# Circuit_Complet_Carrer.net
KiCad netlist of a schematic drawn in Altium Designer
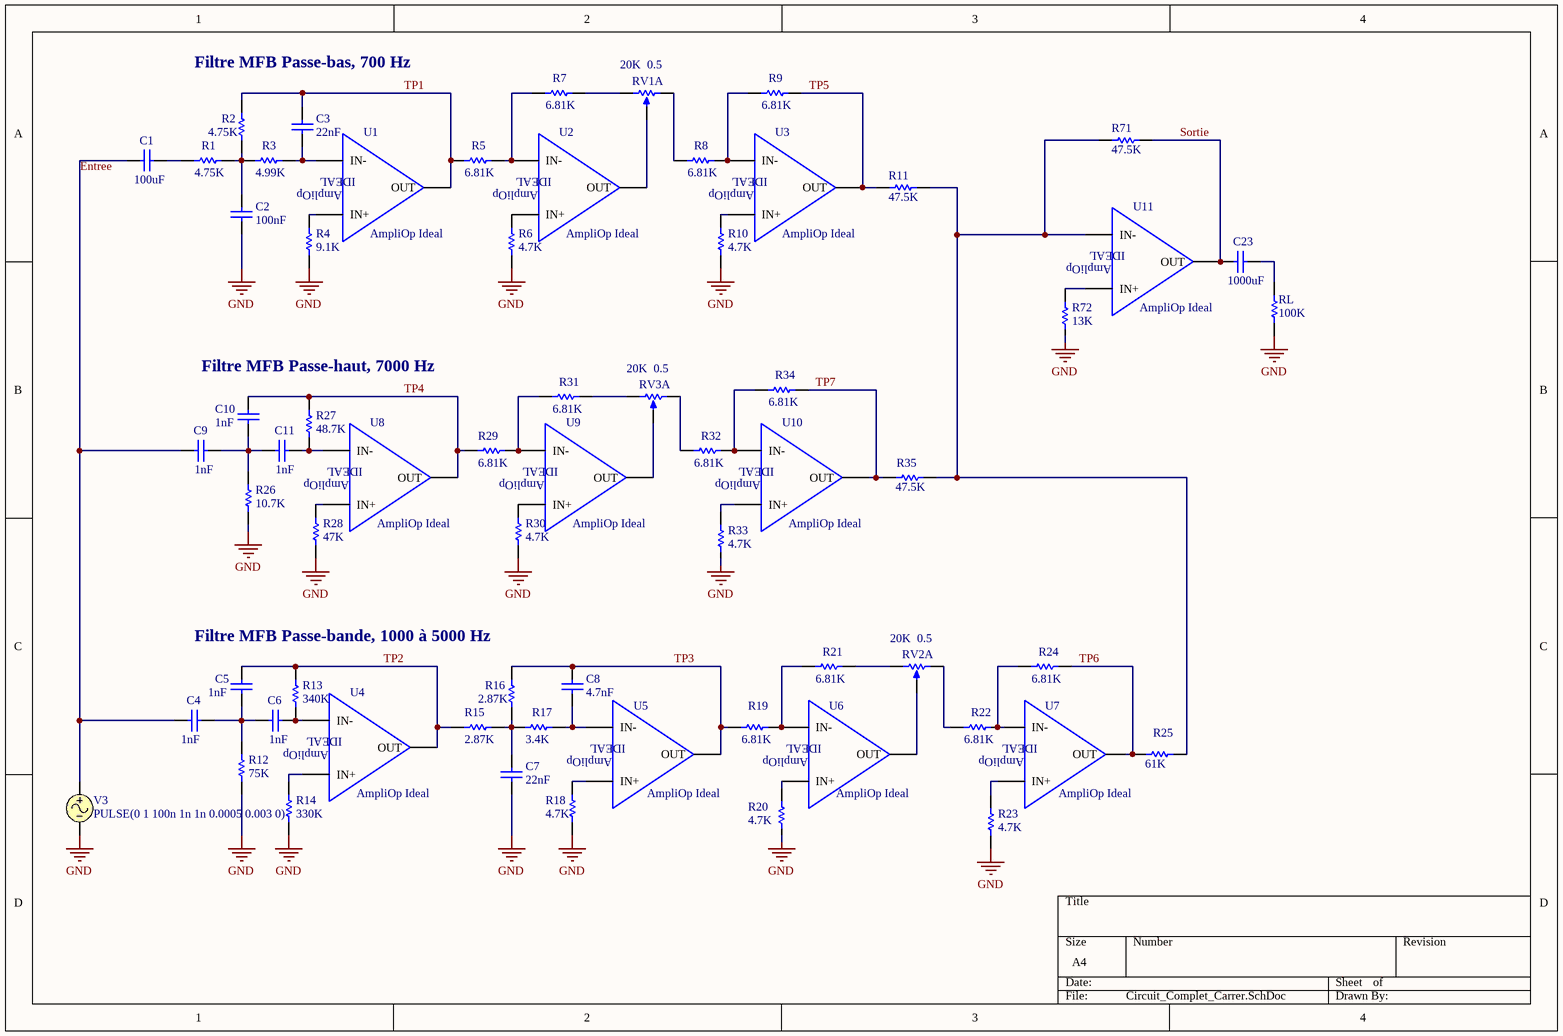
[diagram p0: Circuit_Complet_Carrer.SchDoc]

(export (version "E")
  (design (tool "Eeschema 10.0.6"))
  (components
    (comp (ref "C1")
      (value "100uF")
      (footprint "RAD-0.3")
      (description "Capacitor")
      (fields (field (name "Comment") "Cap") (field (name "PUBLISHER") "Altium Limited"))
      (libsource (lib "Miscellaneous Devices") (part "Cap"))
    )
    (comp (ref "C2")
      (value "100nF")
      (footprint "RAD-0.3")
      (description "Capacitor")
      (fields (field (name "Comment") "Cap") (field (name "PUBLISHER") "Altium Limited"))
      (libsource (lib "Miscellaneous Devices") (part "Cap"))
    )
    (comp (ref "C3")
      (value "22nF")
      (footprint "RAD-0.3")
      (description "Capacitor")
      (fields (field (name "Comment") "Cap") (field (name "PUBLISHER") "Altium Limited"))
      (libsource (lib "Miscellaneous Devices") (part "Cap"))
    )
    (comp (ref "C4")
      (value "1nF")
      (footprint "RAD-0.3")
      (description "Capacitor")
      (fields (field (name "Comment") "Cap") (field (name "PUBLISHER") "Altium Limited"))
      (libsource (lib "Miscellaneous Devices") (part "Cap"))
    )
    (comp (ref "C5")
      (value "1nF")
      (footprint "RAD-0.3")
      (description "Capacitor")
      (fields (field (name "Comment") "Cap") (field (name "PUBLISHER") "Altium Limited"))
      (libsource (lib "Miscellaneous Devices") (part "Cap"))
    )
    (comp (ref "C6")
      (value "1nF")
      (footprint "RAD-0.3")
      (description "Capacitor")
      (fields (field (name "Comment") "Cap") (field (name "PUBLISHER") "Altium Limited"))
      (libsource (lib "Miscellaneous Devices") (part "Cap"))
    )
    (comp (ref "C7")
      (value "22nF")
      (footprint "RAD-0.3")
      (description "Capacitor")
      (fields (field (name "Comment") "Cap") (field (name "PUBLISHER") "Altium Limited"))
      (libsource (lib "Miscellaneous Devices") (part "Cap"))
    )
    (comp (ref "C8")
      (value "4.7nF")
      (footprint "RAD-0.3")
      (description "Capacitor")
      (fields (field (name "Comment") "Cap") (field (name "PUBLISHER") "Altium Limited"))
      (libsource (lib "Miscellaneous Devices") (part "Cap"))
    )
    (comp (ref "C9")
      (value "1nF")
      (footprint "RAD-0.3")
      (description "Capacitor")
      (fields (field (name "Comment") "Cap") (field (name "PUBLISHER") "Altium Limited"))
      (libsource (lib "Miscellaneous Devices") (part "Cap"))
    )
    (comp (ref "C10")
      (value "1nF")
      (footprint "RAD-0.3")
      (description "Capacitor")
      (fields (field (name "Comment") "Cap") (field (name "PUBLISHER") "Altium Limited"))
      (libsource (lib "Miscellaneous Devices") (part "Cap"))
    )
    (comp (ref "C11")
      (value "1nF")
      (footprint "RAD-0.3")
      (description "Capacitor")
      (fields (field (name "Comment") "Cap") (field (name "PUBLISHER") "Altium Limited"))
      (libsource (lib "Miscellaneous Devices") (part "Cap"))
    )
    (comp (ref "C23")
      (value "1000uF")
      (footprint "RAD-0.3")
      (description "Capacitor")
      (fields (field (name "Comment") "Cap") (field (name "PUBLISHER") "Altium Limited"))
      (libsource (lib "Miscellaneous Devices") (part "Cap"))
    )
    (comp (ref "R1")
      (value "4.75K")
      (footprint "AXIAL-0.3")
      (description "Resistor")
      (fields (field (name "Comment") "Res1") (field (name "PUBLISHER") "Altium Limited"))
      (libsource (lib "Miscellaneous Devices") (part "Res1"))
    )
    (comp (ref "R2")
      (value "4.75K")
      (footprint "AXIAL-0.3")
      (description "Resistor")
      (fields (field (name "Comment") "Res1") (field (name "PUBLISHER") "Altium Limited"))
      (libsource (lib "Miscellaneous Devices") (part "Res1"))
    )
    (comp (ref "R3")
      (value "4.99K")
      (footprint "AXIAL-0.3")
      (description "Resistor")
      (fields (field (name "Comment") "Res1") (field (name "PUBLISHER") "Altium Limited"))
      (libsource (lib "Miscellaneous Devices") (part "Res1"))
    )
    (comp (ref "R4")
      (value "9.1K")
      (footprint "AXIAL-0.3")
      (description "Resistor")
      (fields (field (name "Comment") "Res1") (field (name "PUBLISHER") "Altium Limited"))
      (libsource (lib "Miscellaneous Devices") (part "Res1"))
    )
    (comp (ref "R5")
      (value "6.81K")
      (footprint "AXIAL-0.3")
      (description "Resistor")
      (fields (field (name "Comment") "Res1") (field (name "PUBLISHER") "Altium Limited"))
      (libsource (lib "Miscellaneous Devices") (part "Res1"))
    )
    (comp (ref "R6")
      (value "4.7K")
      (footprint "AXIAL-0.3")
      (description "Resistor")
      (fields (field (name "Comment") "Res1") (field (name "PUBLISHER") "Altium Limited"))
      (libsource (lib "Miscellaneous Devices") (part "Res1"))
    )
    (comp (ref "R7")
      (value "6.81K")
      (footprint "AXIAL-0.3")
      (description "Resistor")
      (fields (field (name "Comment") "Res1") (field (name "PUBLISHER") "Altium Limited"))
      (libsource (lib "Miscellaneous Devices") (part "Res1"))
    )
    (comp (ref "R8")
      (value "6.81K")
      (footprint "AXIAL-0.3")
      (description "Resistor")
      (fields (field (name "Comment") "Res1") (field (name "PUBLISHER") "Altium Limited"))
      (libsource (lib "Miscellaneous Devices") (part "Res1"))
    )
    (comp (ref "R9")
      (value "6.81K")
      (footprint "AXIAL-0.3")
      (description "Resistor")
      (fields (field (name "Comment") "Res1") (field (name "PUBLISHER") "Altium Limited"))
      (libsource (lib "Miscellaneous Devices") (part "Res1"))
    )
    (comp (ref "R10")
      (value "4.7K")
      (footprint "AXIAL-0.3")
      (description "Resistor")
      (fields (field (name "Comment") "Res1") (field (name "PUBLISHER") "Altium Limited"))
      (libsource (lib "Miscellaneous Devices") (part "Res1"))
    )
    (comp (ref "R11")
      (value "47.5K")
      (footprint "AXIAL-0.3")
      (description "Resistor")
      (fields (field (name "Comment") "Res1") (field (name "PUBLISHER") "Altium Limited"))
      (libsource (lib "Miscellaneous Devices") (part "Res1"))
    )
    (comp (ref "R12")
      (value "75K")
      (footprint "AXIAL-0.3")
      (description "Resistor")
      (fields (field (name "Comment") "Res1") (field (name "PUBLISHER") "Altium Limited"))
      (libsource (lib "Miscellaneous Devices") (part "Res1"))
    )
    (comp (ref "R13")
      (value "340K")
      (footprint "AXIAL-0.3")
      (description "Resistor")
      (fields (field (name "Comment") "Res1") (field (name "PUBLISHER") "Altium Limited"))
      (libsource (lib "Miscellaneous Devices") (part "Res1"))
    )
    (comp (ref "R14")
      (value "330K")
      (footprint "AXIAL-0.3")
      (description "Resistor")
      (fields (field (name "Comment") "Res1") (field (name "PUBLISHER") "Altium Limited"))
      (libsource (lib "Miscellaneous Devices") (part "Res1"))
    )
    (comp (ref "R15")
      (value "2.87K")
      (footprint "AXIAL-0.3")
      (description "Resistor")
      (fields (field (name "Comment") "Res1") (field (name "PUBLISHER") "Altium Limited"))
      (libsource (lib "Miscellaneous Devices") (part "Res1"))
    )
    (comp (ref "R16")
      (value "2.87K")
      (footprint "AXIAL-0.3")
      (description "Resistor")
      (fields (field (name "Comment") "Res1") (field (name "PUBLISHER") "Altium Limited"))
      (libsource (lib "Miscellaneous Devices") (part "Res1"))
    )
    (comp (ref "R17")
      (value "3.4K")
      (footprint "AXIAL-0.3")
      (description "Resistor")
      (fields (field (name "Comment") "Res1") (field (name "PUBLISHER") "Altium Limited"))
      (libsource (lib "Miscellaneous Devices") (part "Res1"))
    )
    (comp (ref "R18")
      (value "4.7K")
      (footprint "AXIAL-0.3")
      (description "Resistor")
      (fields (field (name "Comment") "Res1") (field (name "PUBLISHER") "Altium Limited"))
      (libsource (lib "Miscellaneous Devices") (part "Res1"))
    )
    (comp (ref "R19")
      (value "6.81K")
      (footprint "AXIAL-0.3")
      (description "Resistor")
      (fields (field (name "Comment") "Res1") (field (name "PUBLISHER") "Altium Limited"))
      (libsource (lib "Miscellaneous Devices") (part "Res1"))
    )
    (comp (ref "R20")
      (value "4.7K")
      (footprint "AXIAL-0.3")
      (description "Resistor")
      (fields (field (name "Comment") "Res1") (field (name "PUBLISHER") "Altium Limited"))
      (libsource (lib "Miscellaneous Devices") (part "Res1"))
    )
    (comp (ref "R21")
      (value "6.81K")
      (footprint "AXIAL-0.3")
      (description "Resistor")
      (fields (field (name "Comment") "Res1") (field (name "PUBLISHER") "Altium Limited"))
      (libsource (lib "Miscellaneous Devices") (part "Res1"))
    )
    (comp (ref "R22")
      (value "6.81K")
      (footprint "AXIAL-0.3")
      (description "Resistor")
      (fields (field (name "Comment") "Res1") (field (name "PUBLISHER") "Altium Limited"))
      (libsource (lib "Miscellaneous Devices") (part "Res1"))
    )
    (comp (ref "R23")
      (value "4.7K")
      (footprint "AXIAL-0.3")
      (description "Resistor")
      (fields (field (name "Comment") "Res1") (field (name "PUBLISHER") "Altium Limited"))
      (libsource (lib "Miscellaneous Devices") (part "Res1"))
    )
    (comp (ref "R24")
      (value "6.81K")
      (footprint "AXIAL-0.3")
      (description "Resistor")
      (fields (field (name "Comment") "Res1") (field (name "PUBLISHER") "Altium Limited"))
      (libsource (lib "Miscellaneous Devices") (part "Res1"))
    )
    (comp (ref "R25")
      (value "61K")
      (footprint "AXIAL-0.3")
      (description "Resistor")
      (fields (field (name "Comment") "Res1") (field (name "PUBLISHER") "Altium Limited"))
      (libsource (lib "Miscellaneous Devices") (part "Res1"))
    )
    (comp (ref "R26")
      (value "10.7K")
      (footprint "AXIAL-0.3")
      (description "Resistor")
      (fields (field (name "Comment") "Res1") (field (name "PUBLISHER") "Altium Limited"))
      (libsource (lib "Miscellaneous Devices") (part "Res1"))
    )
    (comp (ref "R27")
      (value "48.7K")
      (footprint "AXIAL-0.3")
      (description "Resistor")
      (fields (field (name "Comment") "Res1") (field (name "PUBLISHER") "Altium Limited"))
      (libsource (lib "Miscellaneous Devices") (part "Res1"))
    )
    (comp (ref "R28")
      (value "47K")
      (footprint "AXIAL-0.3")
      (description "Resistor")
      (fields (field (name "Comment") "Res1") (field (name "PUBLISHER") "Altium Limited"))
      (libsource (lib "Miscellaneous Devices") (part "Res1"))
    )
    (comp (ref "R29")
      (value "6.81K")
      (footprint "AXIAL-0.3")
      (description "Resistor")
      (fields (field (name "Comment") "Res1") (field (name "PUBLISHER") "Altium Limited"))
      (libsource (lib "Miscellaneous Devices") (part "Res1"))
    )
    (comp (ref "R30")
      (value "4.7K")
      (footprint "AXIAL-0.3")
      (description "Resistor")
      (fields (field (name "Comment") "Res1") (field (name "PUBLISHER") "Altium Limited"))
      (libsource (lib "Miscellaneous Devices") (part "Res1"))
    )
    (comp (ref "R31")
      (value "6.81K")
      (footprint "AXIAL-0.3")
      (description "Resistor")
      (fields (field (name "Comment") "Res1") (field (name "PUBLISHER") "Altium Limited"))
      (libsource (lib "Miscellaneous Devices") (part "Res1"))
    )
    (comp (ref "R32")
      (value "6.81K")
      (footprint "AXIAL-0.3")
      (description "Resistor")
      (fields (field (name "Comment") "Res1") (field (name "PUBLISHER") "Altium Limited"))
      (libsource (lib "Miscellaneous Devices") (part "Res1"))
    )
    (comp (ref "R33")
      (value "4.7K")
      (footprint "AXIAL-0.3")
      (description "Resistor")
      (fields (field (name "Comment") "Res1") (field (name "PUBLISHER") "Altium Limited"))
      (libsource (lib "Miscellaneous Devices") (part "Res1"))
    )
    (comp (ref "R34")
      (value "6.81K")
      (footprint "AXIAL-0.3")
      (description "Resistor")
      (fields (field (name "Comment") "Res1") (field (name "PUBLISHER") "Altium Limited"))
      (libsource (lib "Miscellaneous Devices") (part "Res1"))
    )
    (comp (ref "R35")
      (value "47.5K")
      (footprint "AXIAL-0.3")
      (description "Resistor")
      (fields (field (name "Comment") "Res1") (field (name "PUBLISHER") "Altium Limited"))
      (libsource (lib "Miscellaneous Devices") (part "Res1"))
    )
    (comp (ref "R71")
      (value "47.5K")
      (footprint "AXIAL-0.3")
      (description "Resistor")
      (fields (field (name "Comment") "Res1") (field (name "PUBLISHER") "Altium Limited"))
      (libsource (lib "Miscellaneous Devices") (part "Res1"))
    )
    (comp (ref "R72")
      (value "13K")
      (footprint "AXIAL-0.3")
      (description "Resistor")
      (fields (field (name "Comment") "Res1") (field (name "PUBLISHER") "Altium Limited"))
      (libsource (lib "Miscellaneous Devices") (part "Res1"))
    )
    (comp (ref "RL")
      (value "100K")
      (footprint "AXIAL-0.3")
      (description "Resistor")
      (fields (field (name "Comment") "Res1") (field (name "PUBLISHER") "Altium Limited"))
      (libsource (lib "Miscellaneous Devices") (part "Res1"))
    )
    (comp (ref "RV1A")
      (value "20K")
      (footprint "VR5")
      (description "Potentiometer")
      (fields
        (field (name "SET POSITION") "0.5")
        (field (name "Comment") "RPot")
        (field (name "PUBLISHER") "Altium Limited")
      )
      (libsource (lib "Miscellaneous Devices") (part "RPot"))
    )
    (comp (ref "RV2A")
      (value "20K")
      (footprint "VR5")
      (description "Potentiometer")
      (fields
        (field (name "SET POSITION") "0.5")
        (field (name "Comment") "RPot")
        (field (name "PUBLISHER") "Altium Limited")
      )
      (libsource (lib "Miscellaneous Devices") (part "RPot"))
    )
    (comp (ref "RV3A")
      (value "20K")
      (footprint "VR5")
      (description "Potentiometer")
      (fields
        (field (name "SET POSITION") "0.5")
        (field (name "Comment") "RPot")
        (field (name "PUBLISHER") "Altium Limited")
      )
      (libsource (lib "Miscellaneous Devices") (part "RPot"))
    )
    (comp (ref "U1") (value "AmpliOp Ideal") (libsource (lib "Librarie_S2") (part "AmpliOp_ideal")))
    (comp (ref "U2") (value "AmpliOp Ideal") (libsource (lib "Librarie_S2") (part "AmpliOp_ideal")))
    (comp (ref "U3") (value "AmpliOp Ideal") (libsource (lib "Librarie_S2") (part "AmpliOp_ideal")))
    (comp (ref "U4") (value "AmpliOp Ideal") (libsource (lib "Librarie_S2") (part "AmpliOp_ideal")))
    (comp (ref "U5") (value "AmpliOp Ideal") (libsource (lib "Librarie_S2") (part "AmpliOp_ideal")))
    (comp (ref "U6") (value "AmpliOp Ideal") (libsource (lib "Librarie_S2") (part "AmpliOp_ideal")))
    (comp (ref "U7") (value "AmpliOp Ideal") (libsource (lib "Librarie_S2") (part "AmpliOp_ideal")))
    (comp (ref "U8") (value "AmpliOp Ideal") (libsource (lib "Librarie_S2") (part "AmpliOp_ideal")))
    (comp (ref "U9") (value "AmpliOp Ideal") (libsource (lib "Librarie_S2") (part "AmpliOp_ideal")))
    (comp (ref "U10") (value "AmpliOp Ideal") (libsource (lib "Librarie_S2") (part "AmpliOp_ideal")))
    (comp (ref "U11") (value "AmpliOp Ideal") (libsource (lib "Librarie_S2") (part "AmpliOp_ideal")))
    (comp (ref "V3")
      (value "PULSE(0 1 100n 1n 1n 0.0005 0.003 0)")
      (description "Sinusoidal Voltage Source")
      (fields (field (name "PUBLISHER") "Altium Limited"))
      (libsource (lib "Simulation Sources") (part "VSIN"))
    )
  )
  (nets
    (net (code "1") (name "/Entree") (class "Default")
      (node (ref "C1") (pin "1") (pinfunction "1_1") (pintype "passive"))
      (node (ref "C4") (pin "1") (pinfunction "1_1") (pintype "passive"))
      (node (ref "C9") (pin "1") (pinfunction "1_1") (pintype "passive"))
      (node (ref "V3") (pin "1") (pinfunction "1_1") (pintype "passive"))
    )
    (net (code "2") (name "/Sortie") (class "Default")
      (node (ref "C23") (pin "1") (pinfunction "1_1") (pintype "passive"))
      (node (ref "R71") (pin "2") (pinfunction "2_2") (pintype "passive"))
      (node (ref "U11") (pin "3") (pinfunction "OUT_3") (pintype "passive"))
    )
    (net (code "3") (name "/TP1") (class "Default")
      (node (ref "C3") (pin "1") (pinfunction "1_1") (pintype "passive"))
      (node (ref "R2") (pin "1") (pinfunction "1_1") (pintype "passive"))
      (node (ref "R5") (pin "1") (pinfunction "1_1") (pintype "passive"))
      (node (ref "U1") (pin "3") (pinfunction "OUT_3") (pintype "passive"))
    )
    (net (code "4") (name "/TP2") (class "Default")
      (node (ref "C5") (pin "1") (pinfunction "1_1") (pintype "passive"))
      (node (ref "R13") (pin "1") (pinfunction "1_1") (pintype "passive"))
      (node (ref "R15") (pin "1") (pinfunction "1_1") (pintype "passive"))
      (node (ref "U4") (pin "3") (pinfunction "OUT_3") (pintype "passive"))
    )
    (net (code "5") (name "/TP3") (class "Default")
      (node (ref "C8") (pin "1") (pinfunction "1_1") (pintype "passive"))
      (node (ref "R16") (pin "1") (pinfunction "1_1") (pintype "passive"))
      (node (ref "R19") (pin "1") (pinfunction "1_1") (pintype "passive"))
      (node (ref "U5") (pin "3") (pinfunction "OUT_3") (pintype "passive"))
    )
    (net (code "6") (name "/TP4") (class "Default")
      (node (ref "C10") (pin "1") (pinfunction "1_1") (pintype "passive"))
      (node (ref "R27") (pin "1") (pinfunction "1_1") (pintype "passive"))
      (node (ref "R29") (pin "1") (pinfunction "1_1") (pintype "passive"))
      (node (ref "U8") (pin "3") (pinfunction "OUT_3") (pintype "passive"))
    )
    (net (code "7") (name "/TP5") (class "Default")
      (node (ref "R11") (pin "1") (pinfunction "1_1") (pintype "passive"))
      (node (ref "R9") (pin "2") (pinfunction "2_2") (pintype "passive"))
      (node (ref "U3") (pin "3") (pinfunction "OUT_3") (pintype "passive"))
    )
    (net (code "8") (name "/TP6") (class "Default")
      (node (ref "R24") (pin "2") (pinfunction "2_2") (pintype "passive"))
      (node (ref "R25") (pin "1") (pinfunction "1_1") (pintype "passive"))
      (node (ref "U7") (pin "3") (pinfunction "OUT_3") (pintype "passive"))
    )
    (net (code "9") (name "/TP7") (class "Default")
      (node (ref "R34") (pin "2") (pinfunction "2_2") (pintype "passive"))
      (node (ref "R35") (pin "1") (pinfunction "1_1") (pintype "passive"))
      (node (ref "U10") (pin "3") (pinfunction "OUT_3") (pintype "passive"))
    )
    (net (code "10") (name "GND") (class "Default")
      (node (ref "C2") (pin "2") (pinfunction "2_2") (pintype "passive"))
      (node (ref "C7") (pin "2") (pinfunction "2_2") (pintype "passive"))
      (node (ref "R10") (pin "2") (pinfunction "2_2") (pintype "passive"))
      (node (ref "R12") (pin "2") (pinfunction "2_2") (pintype "passive"))
      (node (ref "R14") (pin "2") (pinfunction "2_2") (pintype "passive"))
      (node (ref "R18") (pin "2") (pinfunction "2_2") (pintype "passive"))
      (node (ref "R20") (pin "2") (pinfunction "2_2") (pintype "passive"))
      (node (ref "R23") (pin "2") (pinfunction "2_2") (pintype "passive"))
      (node (ref "R26") (pin "2") (pinfunction "2_2") (pintype "passive"))
      (node (ref "R28") (pin "2") (pinfunction "2_2") (pintype "passive"))
      (node (ref "R30") (pin "2") (pinfunction "2_2") (pintype "passive"))
      (node (ref "R33") (pin "2") (pinfunction "2_2") (pintype "passive"))
      (node (ref "R4") (pin "2") (pinfunction "2_2") (pintype "passive"))
      (node (ref "R6") (pin "2") (pinfunction "2_2") (pintype "passive"))
      (node (ref "R72") (pin "2") (pinfunction "2_2") (pintype "passive"))
      (node (ref "RL") (pin "1") (pinfunction "1_1") (pintype "passive"))
      (node (ref "V3") (pin "2") (pinfunction "2_2") (pintype "passive"))
    )
    (net (code "11") (name "Net-(C1-Pad2)") (class "Default")
      (node (ref "C1") (pin "2") (pinfunction "2_2") (pintype "passive"))
      (node (ref "R1") (pin "1") (pinfunction "1_1") (pintype "passive"))
    )
    (net (code "12") (name "Net-(C2-Pad1)") (class "Default")
      (node (ref "C2") (pin "1") (pinfunction "1_1") (pintype "passive"))
      (node (ref "R1") (pin "2") (pinfunction "2_2") (pintype "passive"))
      (node (ref "R2") (pin "2") (pinfunction "2_2") (pintype "passive"))
      (node (ref "R3") (pin "1") (pinfunction "1_1") (pintype "passive"))
    )
    (net (code "13") (name "Net-(C4-Pad2)") (class "Default")
      (node (ref "C4") (pin "2") (pinfunction "2_2") (pintype "passive"))
      (node (ref "C5") (pin "2") (pinfunction "2_2") (pintype "passive"))
      (node (ref "C6") (pin "1") (pinfunction "1_1") (pintype "passive"))
      (node (ref "R12") (pin "1") (pinfunction "1_1") (pintype "passive"))
    )
    (net (code "14") (name "Net-(C7-Pad1)") (class "Default")
      (node (ref "C7") (pin "1") (pinfunction "1_1") (pintype "passive"))
      (node (ref "R15") (pin "2") (pinfunction "2_2") (pintype "passive"))
      (node (ref "R16") (pin "2") (pinfunction "2_2") (pintype "passive"))
      (node (ref "R17") (pin "1") (pinfunction "1_1") (pintype "passive"))
    )
    (net (code "15") (name "Net-(C10-Pad2)") (class "Default")
      (node (ref "C10") (pin "2") (pinfunction "2_2") (pintype "passive"))
      (node (ref "C11") (pin "1") (pinfunction "1_1") (pintype "passive"))
      (node (ref "C9") (pin "2") (pinfunction "2_2") (pintype "passive"))
      (node (ref "R26") (pin "1") (pinfunction "1_1") (pintype "passive"))
    )
    (net (code "16") (name "Net-(C23-Pad2)") (class "Default")
      (node (ref "C23") (pin "2") (pinfunction "2_2") (pintype "passive"))
      (node (ref "RL") (pin "2") (pinfunction "2_2") (pintype "passive"))
    )
    (net (code "17") (name "Net-(RV1A-BOT)") (class "Default")
      (node (ref "R8") (pin "1") (pinfunction "1_1") (pintype "passive"))
      (node (ref "RV1A") (pin "2") (pinfunction "BOT_2") (pintype "passive"))
    )
    (net (code "18") (name "Net-(RV1A-TAP)") (class "Default")
      (node (ref "RV1A") (pin "3") (pinfunction "TAP_3") (pintype "passive"))
      (node (ref "U2") (pin "3") (pinfunction "OUT_3") (pintype "passive"))
    )
    (net (code "19") (name "Net-(RV1A-TOP)") (class "Default")
      (node (ref "R7") (pin "2") (pinfunction "2_2") (pintype "passive"))
      (node (ref "RV1A") (pin "1") (pinfunction "TOP_1") (pintype "passive"))
    )
    (net (code "20") (name "Net-(RV2A-BOT)") (class "Default")
      (node (ref "R22") (pin "1") (pinfunction "1_1") (pintype "passive"))
      (node (ref "RV2A") (pin "2") (pinfunction "BOT_2") (pintype "passive"))
    )
    (net (code "21") (name "Net-(RV2A-TAP)") (class "Default")
      (node (ref "RV2A") (pin "3") (pinfunction "TAP_3") (pintype "passive"))
      (node (ref "U6") (pin "3") (pinfunction "OUT_3") (pintype "passive"))
    )
    (net (code "22") (name "Net-(RV2A-TOP)") (class "Default")
      (node (ref "R21") (pin "2") (pinfunction "2_2") (pintype "passive"))
      (node (ref "RV2A") (pin "1") (pinfunction "TOP_1") (pintype "passive"))
    )
    (net (code "23") (name "Net-(RV3A-BOT)") (class "Default")
      (node (ref "R32") (pin "1") (pinfunction "1_1") (pintype "passive"))
      (node (ref "RV3A") (pin "2") (pinfunction "BOT_2") (pintype "passive"))
    )
    (net (code "24") (name "Net-(RV3A-TAP)") (class "Default")
      (node (ref "RV3A") (pin "3") (pinfunction "TAP_3") (pintype "passive"))
      (node (ref "U9") (pin "3") (pinfunction "OUT_3") (pintype "passive"))
    )
    (net (code "25") (name "Net-(RV3A-TOP)") (class "Default")
      (node (ref "R31") (pin "2") (pinfunction "2_2") (pintype "passive"))
      (node (ref "RV3A") (pin "1") (pinfunction "TOP_1") (pintype "passive"))
    )
    (net (code "26") (name "Net-(U1-IN+)") (class "Default")
      (node (ref "R4") (pin "1") (pinfunction "1_1") (pintype "passive"))
      (node (ref "U1") (pin "1") (pinfunction "IN+_1") (pintype "passive"))
    )
    (net (code "27") (name "Net-(U1-IN-)") (class "Default")
      (node (ref "C3") (pin "2") (pinfunction "2_2") (pintype "passive"))
      (node (ref "R3") (pin "2") (pinfunction "2_2") (pintype "passive"))
      (node (ref "U1") (pin "2") (pinfunction "IN-_2") (pintype "passive"))
    )
    (net (code "28") (name "Net-(U2-IN+)") (class "Default")
      (node (ref "R6") (pin "1") (pinfunction "1_1") (pintype "passive"))
      (node (ref "U2") (pin "1") (pinfunction "IN+_1") (pintype "passive"))
    )
    (net (code "29") (name "Net-(U2-IN-)") (class "Default")
      (node (ref "R5") (pin "2") (pinfunction "2_2") (pintype "passive"))
      (node (ref "R7") (pin "1") (pinfunction "1_1") (pintype "passive"))
      (node (ref "U2") (pin "2") (pinfunction "IN-_2") (pintype "passive"))
    )
    (net (code "30") (name "Net-(U3-IN+)") (class "Default")
      (node (ref "R10") (pin "1") (pinfunction "1_1") (pintype "passive"))
      (node (ref "U3") (pin "1") (pinfunction "IN+_1") (pintype "passive"))
    )
    (net (code "31") (name "Net-(U3-IN-)") (class "Default")
      (node (ref "R8") (pin "2") (pinfunction "2_2") (pintype "passive"))
      (node (ref "R9") (pin "1") (pinfunction "1_1") (pintype "passive"))
      (node (ref "U3") (pin "2") (pinfunction "IN-_2") (pintype "passive"))
    )
    (net (code "32") (name "Net-(U4-IN+)") (class "Default")
      (node (ref "R14") (pin "1") (pinfunction "1_1") (pintype "passive"))
      (node (ref "U4") (pin "1") (pinfunction "IN+_1") (pintype "passive"))
    )
    (net (code "33") (name "Net-(U4-IN-)") (class "Default")
      (node (ref "C6") (pin "2") (pinfunction "2_2") (pintype "passive"))
      (node (ref "R13") (pin "2") (pinfunction "2_2") (pintype "passive"))
      (node (ref "U4") (pin "2") (pinfunction "IN-_2") (pintype "passive"))
    )
    (net (code "34") (name "Net-(U5-IN+)") (class "Default")
      (node (ref "R18") (pin "1") (pinfunction "1_1") (pintype "passive"))
      (node (ref "U5") (pin "1") (pinfunction "IN+_1") (pintype "passive"))
    )
    (net (code "35") (name "Net-(U5-IN-)") (class "Default")
      (node (ref "C8") (pin "2") (pinfunction "2_2") (pintype "passive"))
      (node (ref "R17") (pin "2") (pinfunction "2_2") (pintype "passive"))
      (node (ref "U5") (pin "2") (pinfunction "IN-_2") (pintype "passive"))
    )
    (net (code "36") (name "Net-(U6-IN+)") (class "Default")
      (node (ref "R20") (pin "1") (pinfunction "1_1") (pintype "passive"))
      (node (ref "U6") (pin "1") (pinfunction "IN+_1") (pintype "passive"))
    )
    (net (code "37") (name "Net-(U6-IN-)") (class "Default")
      (node (ref "R19") (pin "2") (pinfunction "2_2") (pintype "passive"))
      (node (ref "R21") (pin "1") (pinfunction "1_1") (pintype "passive"))
      (node (ref "U6") (pin "2") (pinfunction "IN-_2") (pintype "passive"))
    )
    (net (code "38") (name "Net-(U7-IN+)") (class "Default")
      (node (ref "R23") (pin "1") (pinfunction "1_1") (pintype "passive"))
      (node (ref "U7") (pin "1") (pinfunction "IN+_1") (pintype "passive"))
    )
    (net (code "39") (name "Net-(U7-IN-)") (class "Default")
      (node (ref "R22") (pin "2") (pinfunction "2_2") (pintype "passive"))
      (node (ref "R24") (pin "1") (pinfunction "1_1") (pintype "passive"))
      (node (ref "U7") (pin "2") (pinfunction "IN-_2") (pintype "passive"))
    )
    (net (code "40") (name "Net-(U8-IN+)") (class "Default")
      (node (ref "R28") (pin "1") (pinfunction "1_1") (pintype "passive"))
      (node (ref "U8") (pin "1") (pinfunction "IN+_1") (pintype "passive"))
    )
    (net (code "41") (name "Net-(U8-IN-)") (class "Default")
      (node (ref "C11") (pin "2") (pinfunction "2_2") (pintype "passive"))
      (node (ref "R27") (pin "2") (pinfunction "2_2") (pintype "passive"))
      (node (ref "U8") (pin "2") (pinfunction "IN-_2") (pintype "passive"))
    )
    (net (code "42") (name "Net-(U9-IN+)") (class "Default")
      (node (ref "R30") (pin "1") (pinfunction "1_1") (pintype "passive"))
      (node (ref "U9") (pin "1") (pinfunction "IN+_1") (pintype "passive"))
    )
    (net (code "43") (name "Net-(U9-IN-)") (class "Default")
      (node (ref "R29") (pin "2") (pinfunction "2_2") (pintype "passive"))
      (node (ref "R31") (pin "1") (pinfunction "1_1") (pintype "passive"))
      (node (ref "U9") (pin "2") (pinfunction "IN-_2") (pintype "passive"))
    )
    (net (code "44") (name "Net-(U10-IN+)") (class "Default")
      (node (ref "R33") (pin "1") (pinfunction "1_1") (pintype "passive"))
      (node (ref "U10") (pin "1") (pinfunction "IN+_1") (pintype "passive"))
    )
    (net (code "45") (name "Net-(U10-IN-)") (class "Default")
      (node (ref "R32") (pin "2") (pinfunction "2_2") (pintype "passive"))
      (node (ref "R34") (pin "1") (pinfunction "1_1") (pintype "passive"))
      (node (ref "U10") (pin "2") (pinfunction "IN-_2") (pintype "passive"))
    )
    (net (code "46") (name "Net-(U11-IN+)") (class "Default")
      (node (ref "R72") (pin "1") (pinfunction "1_1") (pintype "passive"))
      (node (ref "U11") (pin "1") (pinfunction "IN+_1") (pintype "passive"))
    )
    (net (code "47") (name "Net-(U11-IN-)") (class "Default")
      (node (ref "R11") (pin "2") (pinfunction "2_2") (pintype "passive"))
      (node (ref "R25") (pin "2") (pinfunction "2_2") (pintype "passive"))
      (node (ref "R35") (pin "2") (pinfunction "2_2") (pintype "passive"))
      (node (ref "R71") (pin "1") (pinfunction "1_1") (pintype "passive"))
      (node (ref "U11") (pin "2") (pinfunction "IN-_2") (pintype "passive"))
    )
  )
)
